# W532X.net
KiCad netlist of a schematic drawn in EAGLE
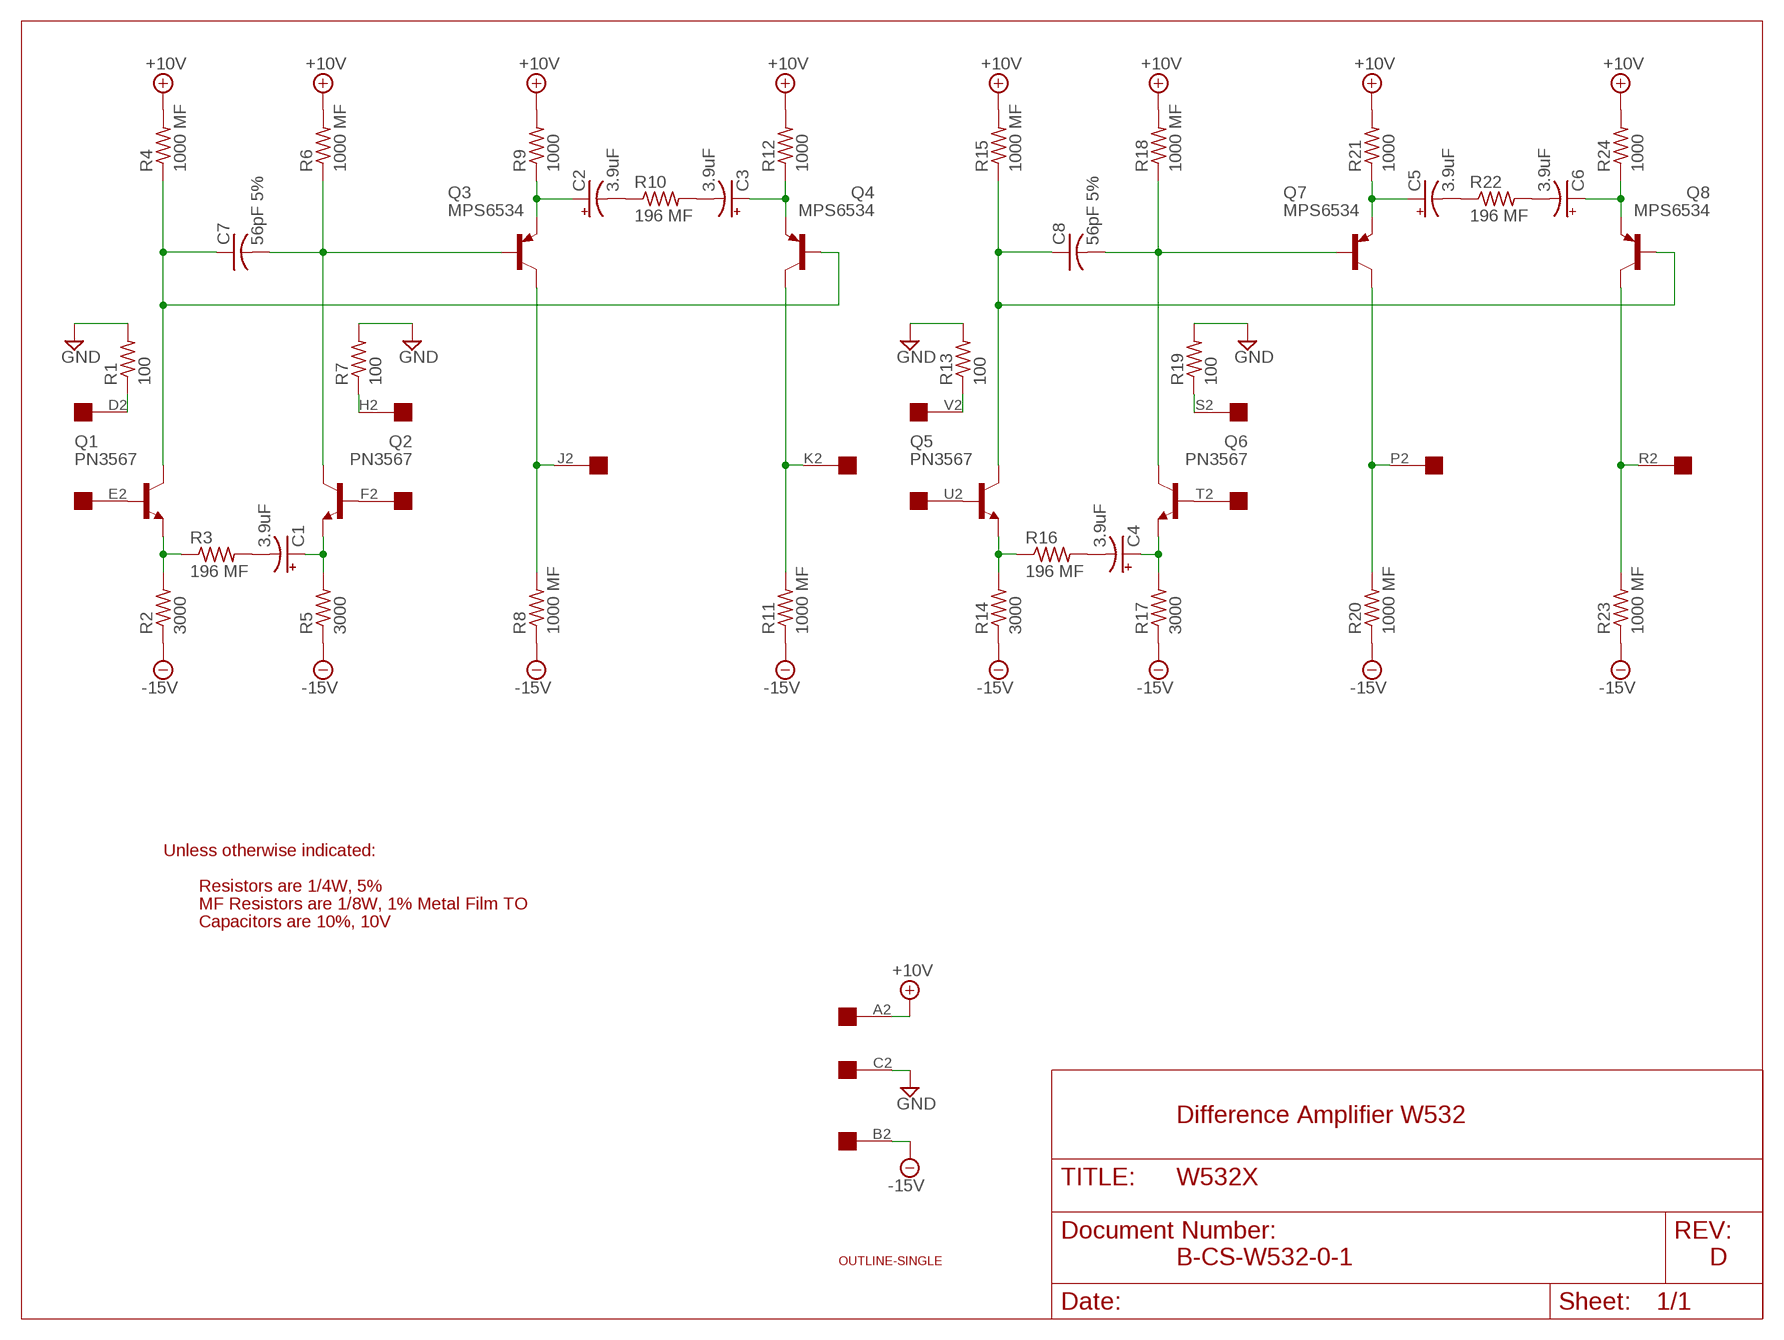
[diagram p0: schematic, sheet 1]

(export (version "E")
  (design (tool "Eeschema 10.0.6"))
  (components
    (comp (ref "C1")
      (value "3.9uF")
      (footprint "eagle-import:E15-5")
      (libsource (lib "eagle-import") (part "CPOL-USE15-5AXIAL"))
    )
    (comp (ref "C2")
      (value "3.9uF")
      (footprint "eagle-import:E15-5")
      (libsource (lib "eagle-import") (part "CPOL-USE15-5AXIAL"))
    )
    (comp (ref "C3")
      (value "3.9uF")
      (footprint "eagle-import:E15-5")
      (libsource (lib "eagle-import") (part "CPOL-USE15-5AXIAL"))
    )
    (comp (ref "C4")
      (value "3.9uF")
      (footprint "eagle-import:E15-5")
      (libsource (lib "eagle-import") (part "CPOL-USE15-5AXIAL"))
    )
    (comp (ref "C5")
      (value "3.9uF")
      (footprint "eagle-import:E15-5")
      (libsource (lib "eagle-import") (part "CPOL-USE15-5AXIAL"))
    )
    (comp (ref "C6")
      (value "3.9uF")
      (footprint "eagle-import:E15-5")
      (libsource (lib "eagle-import") (part "CPOL-USE15-5AXIAL"))
    )
    (comp (ref "C7")
      (value "56pF 5%")
      (footprint "eagle-import:C150-054X183")
      (libsource (lib "eagle-import") (part "C-US150-054X183"))
    )
    (comp (ref "C8")
      (value "56pF 5%")
      (footprint "eagle-import:C150-054X183")
      (libsource (lib "eagle-import") (part "C-US150-054X183"))
    )
    (comp (ref "Q1")
      (value "PN3567")
      (footprint "eagle-import:TO5")
      (libsource (lib "eagle-import") (part "2N2102"))
    )
    (comp (ref "Q2")
      (value "PN3567")
      (footprint "eagle-import:TO5")
      (libsource (lib "eagle-import") (part "2N2102"))
    )
    (comp (ref "Q3")
      (value "MPS6534")
      (footprint "eagle-import:TO39")
      (libsource (lib "eagle-import") (part "2N2904"))
    )
    (comp (ref "Q4")
      (value "MPS6534")
      (footprint "eagle-import:TO39")
      (libsource (lib "eagle-import") (part "2N2904"))
    )
    (comp (ref "Q5")
      (value "PN3567")
      (footprint "eagle-import:TO5")
      (libsource (lib "eagle-import") (part "2N2102"))
    )
    (comp (ref "Q6")
      (value "PN3567")
      (footprint "eagle-import:TO5")
      (libsource (lib "eagle-import") (part "2N2102"))
    )
    (comp (ref "Q7")
      (value "MPS6534")
      (footprint "eagle-import:TO39")
      (libsource (lib "eagle-import") (part "2N2904"))
    )
    (comp (ref "Q8")
      (value "MPS6534")
      (footprint "eagle-import:TO39")
      (libsource (lib "eagle-import") (part "2N2904"))
    )
    (comp (ref "R1")
      (value "100")
      (footprint "eagle-import:0207_10")
      (libsource (lib "eagle-import") (part "R-US_0207/10"))
    )
    (comp (ref "R2")
      (value "3000")
      (footprint "eagle-import:0207_10")
      (libsource (lib "eagle-import") (part "R-US_0207/10"))
    )
    (comp (ref "R3")
      (value "196 MF")
      (footprint "eagle-import:0207_15")
      (libsource (lib "eagle-import") (part "R-US_0207/15"))
    )
    (comp (ref "R4")
      (value "1000 MF")
      (footprint "eagle-import:0207_15")
      (libsource (lib "eagle-import") (part "R-US_0207/15"))
    )
    (comp (ref "R5")
      (value "3000")
      (footprint "eagle-import:0207_10")
      (libsource (lib "eagle-import") (part "R-US_0207/10"))
    )
    (comp (ref "R6")
      (value "1000 MF")
      (footprint "eagle-import:0207_15")
      (libsource (lib "eagle-import") (part "R-US_0207/15"))
    )
    (comp (ref "R7")
      (value "100")
      (footprint "eagle-import:0207_10")
      (libsource (lib "eagle-import") (part "R-US_0207/10"))
    )
    (comp (ref "R8")
      (value "1000 MF")
      (footprint "eagle-import:0207_15")
      (libsource (lib "eagle-import") (part "R-US_0207/15"))
    )
    (comp (ref "R9")
      (value "1000")
      (footprint "eagle-import:0207_10")
      (libsource (lib "eagle-import") (part "R-US_0207/10"))
    )
    (comp (ref "R10")
      (value "196 MF")
      (footprint "eagle-import:0207_15")
      (libsource (lib "eagle-import") (part "R-US_0207/15"))
    )
    (comp (ref "R11")
      (value "1000 MF")
      (footprint "eagle-import:0207_15")
      (libsource (lib "eagle-import") (part "R-US_0207/15"))
    )
    (comp (ref "R12")
      (value "1000")
      (footprint "eagle-import:0207_10")
      (libsource (lib "eagle-import") (part "R-US_0207/10"))
    )
    (comp (ref "R13")
      (value "100")
      (footprint "eagle-import:0207_10")
      (libsource (lib "eagle-import") (part "R-US_0207/10"))
    )
    (comp (ref "R14")
      (value "3000")
      (footprint "eagle-import:0207_10")
      (libsource (lib "eagle-import") (part "R-US_0207/10"))
    )
    (comp (ref "R15")
      (value "1000 MF")
      (footprint "eagle-import:0207_15")
      (libsource (lib "eagle-import") (part "R-US_0207/15"))
    )
    (comp (ref "R16")
      (value "196 MF")
      (footprint "eagle-import:0207_15")
      (libsource (lib "eagle-import") (part "R-US_0207/15"))
    )
    (comp (ref "R17")
      (value "3000")
      (footprint "eagle-import:0207_10")
      (libsource (lib "eagle-import") (part "R-US_0207/10"))
    )
    (comp (ref "R18")
      (value "1000 MF")
      (footprint "eagle-import:0207_15")
      (libsource (lib "eagle-import") (part "R-US_0207/15"))
    )
    (comp (ref "R19")
      (value "100")
      (footprint "eagle-import:0207_10")
      (libsource (lib "eagle-import") (part "R-US_0207/10"))
    )
    (comp (ref "R20")
      (value "1000 MF")
      (footprint "eagle-import:0207_15")
      (libsource (lib "eagle-import") (part "R-US_0207/15"))
    )
    (comp (ref "R21")
      (value "1000")
      (footprint "eagle-import:0207_10")
      (libsource (lib "eagle-import") (part "R-US_0207/10"))
    )
    (comp (ref "R22")
      (value "196 MF")
      (footprint "eagle-import:0207_15")
      (libsource (lib "eagle-import") (part "R-US_0207/15"))
    )
    (comp (ref "R23")
      (value "1000 MF")
      (footprint "eagle-import:0207_15")
      (libsource (lib "eagle-import") (part "R-US_0207/15"))
    )
    (comp (ref "R24")
      (value "1000")
      (footprint "eagle-import:0207_10")
      (libsource (lib "eagle-import") (part "R-US_0207/10"))
    )
    (comp (ref "U$1")
      (value "OUTLINE-SINGLE")
      (footprint "eagle-import:SINGLE")
      (libsource (lib "eagle-import") (part "OUTLINE-SINGLE"))
    )
    (comp (ref "U$2")
      (value "EDGE-1")
      (footprint "eagle-import:EDGE-CON1")
      (libsource (lib "eagle-import") (part "EDGE-1"))
    )
  )
  (nets
    (net (code "1") (name "+10V") (class "Default")
      (node (ref "R12") (pin "2") (pinfunction "2_2") (pintype "passive"))
      (node (ref "R15") (pin "2") (pinfunction "2_2") (pintype "passive"))
      (node (ref "R18") (pin "2") (pinfunction "2_2") (pintype "passive"))
      (node (ref "R21") (pin "2") (pinfunction "2_2") (pintype "passive"))
      (node (ref "R24") (pin "2") (pinfunction "2_2") (pintype "passive"))
      (node (ref "R4") (pin "2") (pinfunction "2_2") (pintype "passive"))
      (node (ref "R6") (pin "2") (pinfunction "2_2") (pintype "passive"))
      (node (ref "R9") (pin "2") (pinfunction "2_2") (pintype "passive"))
      (node (ref "U$2") (pin "A2") (pinfunction "1_A2") (pintype "bidirectional"))
    )
    (net (code "2") (name "-15V") (class "Default")
      (node (ref "R11") (pin "1") (pinfunction "1_1") (pintype "passive"))
      (node (ref "R14") (pin "1") (pinfunction "1_1") (pintype "passive"))
      (node (ref "R17") (pin "1") (pinfunction "1_1") (pintype "passive"))
      (node (ref "R2") (pin "1") (pinfunction "1_1") (pintype "passive"))
      (node (ref "R20") (pin "1") (pinfunction "1_1") (pintype "passive"))
      (node (ref "R23") (pin "1") (pinfunction "1_1") (pintype "passive"))
      (node (ref "R5") (pin "1") (pinfunction "1_1") (pintype "passive"))
      (node (ref "R8") (pin "1") (pinfunction "1_1") (pintype "passive"))
      (node (ref "U$2") (pin "B2") (pinfunction "1_B2") (pintype "bidirectional"))
    )
    (net (code "3") (name "GND") (class "Default")
      (node (ref "R1") (pin "2") (pinfunction "2_2") (pintype "passive"))
      (node (ref "R13") (pin "2") (pinfunction "2_2") (pintype "passive"))
      (node (ref "R19") (pin "2") (pinfunction "2_2") (pintype "passive"))
      (node (ref "R7") (pin "2") (pinfunction "2_2") (pintype "passive"))
      (node (ref "U$2") (pin "C2") (pinfunction "1_C2") (pintype "bidirectional"))
    )
    (net (code "4") (name "Net-(C1-Pad-)") (class "Default")
      (node (ref "C1") (pin "-") (pinfunction "-_-") (pintype "passive"))
      (node (ref "R3") (pin "2") (pinfunction "2_2") (pintype "passive"))
    )
    (net (code "5") (name "Net-(C2-Pad-)") (class "Default")
      (node (ref "C2") (pin "-") (pinfunction "-_-") (pintype "passive"))
      (node (ref "R10") (pin "1") (pinfunction "1_1") (pintype "passive"))
    )
    (net (code "6") (name "Net-(C3-Pad-)") (class "Default")
      (node (ref "C3") (pin "-") (pinfunction "-_-") (pintype "passive"))
      (node (ref "R10") (pin "2") (pinfunction "2_2") (pintype "passive"))
    )
    (net (code "7") (name "Net-(C4-Pad-)") (class "Default")
      (node (ref "C4") (pin "-") (pinfunction "-_-") (pintype "passive"))
      (node (ref "R16") (pin "2") (pinfunction "2_2") (pintype "passive"))
    )
    (net (code "8") (name "Net-(C5-Pad-)") (class "Default")
      (node (ref "C5") (pin "-") (pinfunction "-_-") (pintype "passive"))
      (node (ref "R22") (pin "1") (pinfunction "1_1") (pintype "passive"))
    )
    (net (code "9") (name "Net-(C6-Pad-)") (class "Default")
      (node (ref "C6") (pin "-") (pinfunction "-_-") (pintype "passive"))
      (node (ref "R22") (pin "2") (pinfunction "2_2") (pintype "passive"))
    )
    (net (code "10") (name "Net-(Q1-B)") (class "Default")
      (node (ref "Q1") (pin "2") (pinfunction "B_2") (pintype "passive"))
      (node (ref "U$2") (pin "E2") (pinfunction "1_E2") (pintype "bidirectional"))
    )
    (net (code "11") (name "Net-(Q1-C)") (class "Default")
      (node (ref "C7") (pin "1") (pinfunction "1_1") (pintype "passive"))
      (node (ref "Q1") (pin "3") (pinfunction "C_3") (pintype "passive"))
      (node (ref "Q4") (pin "2") (pinfunction "B_2") (pintype "passive"))
      (node (ref "R4") (pin "1") (pinfunction "1_1") (pintype "passive"))
    )
    (net (code "12") (name "Net-(Q1-E)") (class "Default")
      (node (ref "Q1") (pin "1") (pinfunction "E_1") (pintype "passive"))
      (node (ref "R2") (pin "2") (pinfunction "2_2") (pintype "passive"))
      (node (ref "R3") (pin "1") (pinfunction "1_1") (pintype "passive"))
    )
    (net (code "13") (name "Net-(Q2-B)") (class "Default")
      (node (ref "Q2") (pin "2") (pinfunction "B_2") (pintype "passive"))
      (node (ref "U$2") (pin "F2") (pinfunction "1_F2") (pintype "bidirectional"))
    )
    (net (code "14") (name "Net-(Q2-C)") (class "Default")
      (node (ref "C7") (pin "2") (pinfunction "2_2") (pintype "passive"))
      (node (ref "Q2") (pin "3") (pinfunction "C_3") (pintype "passive"))
      (node (ref "Q3") (pin "2") (pinfunction "B_2") (pintype "passive"))
      (node (ref "R6") (pin "1") (pinfunction "1_1") (pintype "passive"))
    )
    (net (code "15") (name "Net-(Q2-E)") (class "Default")
      (node (ref "C1") (pin "+") (pinfunction "+_+") (pintype "passive"))
      (node (ref "Q2") (pin "1") (pinfunction "E_1") (pintype "passive"))
      (node (ref "R5") (pin "2") (pinfunction "2_2") (pintype "passive"))
    )
    (net (code "16") (name "Net-(Q3-C)") (class "Default")
      (node (ref "Q3") (pin "3") (pinfunction "C_3") (pintype "passive"))
      (node (ref "R8") (pin "2") (pinfunction "2_2") (pintype "passive"))
      (node (ref "U$2") (pin "J2") (pinfunction "1_J2") (pintype "bidirectional"))
    )
    (net (code "17") (name "Net-(Q3-E)") (class "Default")
      (node (ref "C2") (pin "+") (pinfunction "+_+") (pintype "passive"))
      (node (ref "Q3") (pin "1") (pinfunction "E_1") (pintype "passive"))
      (node (ref "R9") (pin "1") (pinfunction "1_1") (pintype "passive"))
    )
    (net (code "18") (name "Net-(Q4-C)") (class "Default")
      (node (ref "Q4") (pin "3") (pinfunction "C_3") (pintype "passive"))
      (node (ref "R11") (pin "2") (pinfunction "2_2") (pintype "passive"))
      (node (ref "U$2") (pin "K2") (pinfunction "1_K2") (pintype "bidirectional"))
    )
    (net (code "19") (name "Net-(Q4-E)") (class "Default")
      (node (ref "C3") (pin "+") (pinfunction "+_+") (pintype "passive"))
      (node (ref "Q4") (pin "1") (pinfunction "E_1") (pintype "passive"))
      (node (ref "R12") (pin "1") (pinfunction "1_1") (pintype "passive"))
    )
    (net (code "20") (name "Net-(Q5-B)") (class "Default")
      (node (ref "Q5") (pin "2") (pinfunction "B_2") (pintype "passive"))
      (node (ref "U$2") (pin "U2") (pinfunction "1_U2") (pintype "bidirectional"))
    )
    (net (code "21") (name "Net-(Q5-C)") (class "Default")
      (node (ref "C8") (pin "1") (pinfunction "1_1") (pintype "passive"))
      (node (ref "Q5") (pin "3") (pinfunction "C_3") (pintype "passive"))
      (node (ref "Q8") (pin "2") (pinfunction "B_2") (pintype "passive"))
      (node (ref "R15") (pin "1") (pinfunction "1_1") (pintype "passive"))
    )
    (net (code "22") (name "Net-(Q5-E)") (class "Default")
      (node (ref "Q5") (pin "1") (pinfunction "E_1") (pintype "passive"))
      (node (ref "R14") (pin "2") (pinfunction "2_2") (pintype "passive"))
      (node (ref "R16") (pin "1") (pinfunction "1_1") (pintype "passive"))
    )
    (net (code "23") (name "Net-(Q6-B)") (class "Default")
      (node (ref "Q6") (pin "2") (pinfunction "B_2") (pintype "passive"))
      (node (ref "U$2") (pin "T2") (pinfunction "1_T2") (pintype "bidirectional"))
    )
    (net (code "24") (name "Net-(Q6-C)") (class "Default")
      (node (ref "C8") (pin "2") (pinfunction "2_2") (pintype "passive"))
      (node (ref "Q6") (pin "3") (pinfunction "C_3") (pintype "passive"))
      (node (ref "Q7") (pin "2") (pinfunction "B_2") (pintype "passive"))
      (node (ref "R18") (pin "1") (pinfunction "1_1") (pintype "passive"))
    )
    (net (code "25") (name "Net-(Q6-E)") (class "Default")
      (node (ref "C4") (pin "+") (pinfunction "+_+") (pintype "passive"))
      (node (ref "Q6") (pin "1") (pinfunction "E_1") (pintype "passive"))
      (node (ref "R17") (pin "2") (pinfunction "2_2") (pintype "passive"))
    )
    (net (code "26") (name "Net-(Q7-C)") (class "Default")
      (node (ref "Q7") (pin "3") (pinfunction "C_3") (pintype "passive"))
      (node (ref "R20") (pin "2") (pinfunction "2_2") (pintype "passive"))
      (node (ref "U$2") (pin "P2") (pinfunction "1_P2") (pintype "bidirectional"))
    )
    (net (code "27") (name "Net-(Q7-E)") (class "Default")
      (node (ref "C5") (pin "+") (pinfunction "+_+") (pintype "passive"))
      (node (ref "Q7") (pin "1") (pinfunction "E_1") (pintype "passive"))
      (node (ref "R21") (pin "1") (pinfunction "1_1") (pintype "passive"))
    )
    (net (code "28") (name "Net-(Q8-C)") (class "Default")
      (node (ref "Q8") (pin "3") (pinfunction "C_3") (pintype "passive"))
      (node (ref "R23") (pin "2") (pinfunction "2_2") (pintype "passive"))
      (node (ref "U$2") (pin "R2") (pinfunction "1_R2") (pintype "bidirectional"))
    )
    (net (code "29") (name "Net-(Q8-E)") (class "Default")
      (node (ref "C6") (pin "+") (pinfunction "+_+") (pintype "passive"))
      (node (ref "Q8") (pin "1") (pinfunction "E_1") (pintype "passive"))
      (node (ref "R24") (pin "1") (pinfunction "1_1") (pintype "passive"))
    )
    (net (code "30") (name "Net-(U$2D-1)") (class "Default")
      (node (ref "R1") (pin "1") (pinfunction "1_1") (pintype "passive"))
      (node (ref "U$2") (pin "D2") (pinfunction "1_D2") (pintype "bidirectional"))
    )
    (net (code "31") (name "Net-(U$2G-1)") (class "Default")
      (node (ref "R7") (pin "1") (pinfunction "1_1") (pintype "passive"))
      (node (ref "U$2") (pin "H2") (pinfunction "1_H2") (pintype "bidirectional"))
    )
    (net (code "32") (name "Net-(U$2O-1)") (class "Default")
      (node (ref "R19") (pin "1") (pinfunction "1_1") (pintype "passive"))
      (node (ref "U$2") (pin "S2") (pinfunction "1_S2") (pintype "bidirectional"))
    )
    (net (code "33") (name "Net-(U$2R-1)") (class "Default")
      (node (ref "R13") (pin "1") (pinfunction "1_1") (pintype "passive"))
      (node (ref "U$2") (pin "V2") (pinfunction "1_V2") (pintype "bidirectional"))
    )
  )
)
